# LM2596.net
KiCad netlist of a schematic drawn in Altium Designer
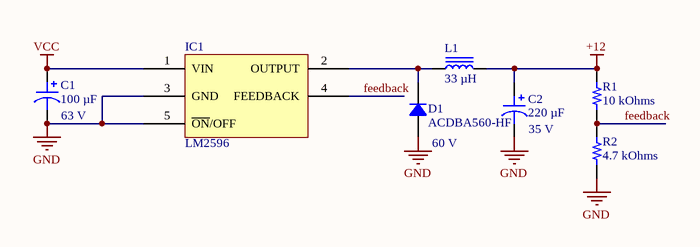
[diagram p0: LM2596.SchDoc]

(export (version "E")
  (design (tool "Eeschema 10.0.6"))
  (components
    (comp (ref "C1")
      (value "100 µF")
      (footprint "CAP AL TH D8 L3.5 H12.5")
      (description "CAP ALUM 100UF 20% 63V RADIAL")
      (fields
        (field (name "PART NUMBER") "ECA-1JM101")
        (field (name "MANUFACTURER") "Panasonic Electronic Components")
        (field (name "VOLTAGE - RATED") "63 V")
      )
      (libsource (lib "Celestial Altium Library - altium_library (1)") (part "Polarised Capacitor"))
    )
    (comp (ref "C2")
      (value "220 µF")
      (footprint "CAP AL TH D8 L3.5 H12.5")
      (description "CAP ALUM 220UF 20% 35V RADIAL")
      (fields
        (field (name "PART NUMBER") "ECA-1VM221")
        (field (name "MANUFACTURER") "Panasonic Electronic Components")
        (field (name "VOLTAGE - RATED") "35 V")
      )
      (libsource (lib "Celestial Altium Library - altium_library (1)") (part "Polarised Capacitor"))
    )
    (comp (ref "D1")
      (value "ACDBA560-HF")
      (footprint "DO214AC SMA")
      (description "DIODE SCHOTTKY 60V 5A DO214AC")
      (fields
        (field (name "MANUFACTURER") "Comchip Technology")
        (field (name "VOLTAGE - DC REVERSE (VR) (MAX)") "60 V")
      )
      (libsource (lib "Celestial Altium Library - altium_library (1)") (part "Diode"))
    )
    (comp (ref "IC1")
      (value "LM2596")
      (footprint "LM2596:D2PAK")
      (libsource (lib "altiumlive") (part "LM2596"))
    )
    (comp (ref "L1")
      (value "33 µH")
      (footprint "BOURNS SRR1280")
      (description "FIXED IND 33UH 3.5A 57 MOHM SMD")
      (fields (field (name "PART NUMBER") "SRR1280-330M") (field (name "MANUFACTURER") "Bourns Inc."))
      (libsource (lib "Celestial Altium Library - altium_library (1)") (part "Inductor"))
    )
    (comp (ref "R1")
      (value "10 kOhms")
      (footprint "RES 0805_2012")
      (description "RES SMD 10K OHM 1% 1/8W 0805")
      (fields
        (field (name "PART NUMBER") "CRG0805F10K")
        (field (name "MANUFACTURER") "TE Connectivity Passive Product")
      )
      (libsource (lib "Celestial Altium Library - altium_library (1)") (part "Resistor"))
    )
    (comp (ref "R2")
      (value "4.7 kOhms")
      (footprint "RES 0805_2012")
      (description "RES SMD 4.7K OHM 1% 1/8W 0805")
      (fields
        (field (name "PART NUMBER") "CRG0805F4K7")
        (field (name "MANUFACTURER") "TE Connectivity Passive Product")
      )
      (libsource (lib "Celestial Altium Library - altium_library (1)") (part "Resistor"))
    )
  )
  (nets
    (net (code "1") (name "+12") (class "Default")
      (node (ref "C2") (pin "1") (pinfunction "1_1") (pintype "passive"))
      (node (ref "L1") (pin "2") (pinfunction "2_2") (pintype "passive"))
      (node (ref "R1") (pin "2") (pinfunction "2_2") (pintype "passive"))
    )
    (net (code "2") (name "/feedback") (class "Default")
      (node (ref "IC1") (pin "4") (pinfunction "FEEDBACK_4") (pintype "passive"))
      (node (ref "R1") (pin "1") (pinfunction "1_1") (pintype "passive"))
      (node (ref "R2") (pin "2") (pinfunction "2_2") (pintype "passive"))
    )
    (net (code "3") (name "GND") (class "Default")
      (node (ref "C1") (pin "2") (pinfunction "2_2") (pintype "passive"))
      (node (ref "C2") (pin "2") (pinfunction "2_2") (pintype "passive"))
      (node (ref "D1") (pin "1") (pinfunction "1_1") (pintype "passive"))
      (node (ref "IC1") (pin "3") (pinfunction "GND_3") (pintype "passive"))
      (node (ref "IC1") (pin "5") (pinfunction "~{ON}/OFF_5") (pintype "passive"))
      (node (ref "R2") (pin "1") (pinfunction "1_1") (pintype "passive"))
    )
    (net (code "4") (name "Net-(IC1-OUTPUT)") (class "Default")
      (node (ref "D1") (pin "2") (pinfunction "2_2") (pintype "passive"))
      (node (ref "IC1") (pin "2") (pinfunction "OUTPUT_2") (pintype "passive"))
      (node (ref "L1") (pin "1") (pinfunction "1_1") (pintype "passive"))
    )
    (net (code "5") (name "VCC") (class "Default")
      (node (ref "C1") (pin "1") (pinfunction "1_1") (pintype "passive"))
      (node (ref "IC1") (pin "1") (pinfunction "VIN_1") (pintype "passive"))
    )
  )
)
